# UART_Comm_Isolation.net
KiCad netlist of a schematic drawn in Altium Designer
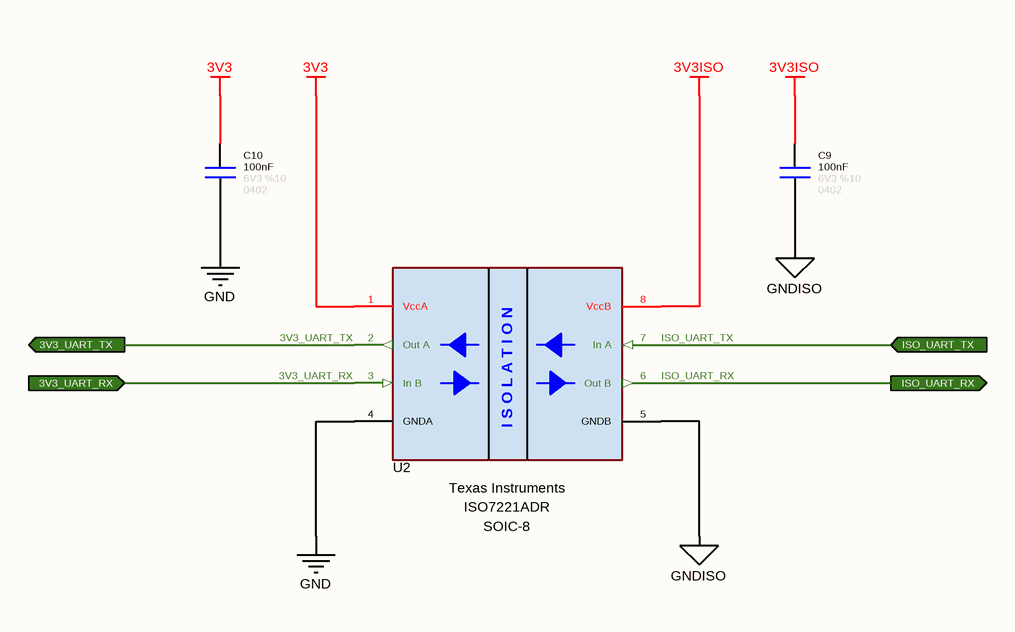
[diagram p0: UART Comm Isolation.SchDoc]

(export (version "E")
  (design (tool "Eeschema 10.0.6"))
  (components
    (comp (ref "C9")
      (value "100nF")
      (footprint "CAPACITOR_0402")
      (description "Capacitor - 100nF [0402-6V3] (Ceramic)")
      (fields
        (field (name "MANUFACTURER PART NUMBER") "04026D104KAT4A")
        (field (name "TOLERANCE") "%10")
        (field (name "VOLTAGE") "6V3")
        (field (name "CASE") "0402")
        (field (name "Comment") "Capacitor - 100nF [0402] (Ceramic)")
      )
      (libsource (lib "Akkoyun") (part "Capacitor - 100nF [0402-6V3]"))
    )
    (comp (ref "C10")
      (value "100nF")
      (footprint "CAPACITOR_0402")
      (description "Capacitor - 100nF [0402-6V3] (Ceramic)")
      (fields
        (field (name "MANUFACTURER PART NUMBER") "04026D104KAT4A")
        (field (name "TOLERANCE") "%10")
        (field (name "VOLTAGE") "6V3")
        (field (name "CASE") "0402")
        (field (name "Comment") "Capacitor - 100nF [0402] (Ceramic)")
      )
      (libsource (lib "Akkoyun") (part "Capacitor - 100nF [0402-6V3]"))
    )
    (comp (ref "U2")
      (value "ISO7221ADR")
      (footprint "SOIC-8 Narrow")
      (description "Dual-channel, TTL, 1/1, 1-Mbps digital isolator 8-SOIC -40 to 125")
      (fields
        (field (name "MANUFACTURER NAME") "Texas Instruments")
        (field (name "MANUFACTURER PART NUMBER") "ISO7221ADR")
        (field (name "CASE") "SOIC-8")
      )
      (libsource (lib "Akkoyun") (part "IC - ISO7221ADR"))
    )
  )
  (nets
    (net (code "1") (name "/3V3_UART_RX") (class "Default")
      (node (ref "U2") (pin "3") (pinfunction "In_B_3") (pintype "input"))
    )
    (net (code "2") (name "/3V3_UART_TX") (class "Default")
      (node (ref "U2") (pin "2") (pinfunction "Out_A_2") (pintype "output"))
    )
    (net (code "3") (name "/ISO_UART_RX") (class "Default")
      (node (ref "U2") (pin "6") (pinfunction "Out_B_6") (pintype "output"))
    )
    (net (code "4") (name "/ISO_UART_TX") (class "Default")
      (node (ref "U2") (pin "7") (pinfunction "In_A_7") (pintype "input"))
    )
    (net (code "5") (name "3V3") (class "Default")
      (node (ref "C10") (pin "2") (pinfunction "2_2") (pintype "passive"))
      (node (ref "U2") (pin "1") (pinfunction "VccA_1") (pintype "power_in"))
    )
    (net (code "6") (name "3V3ISO") (class "Default")
      (node (ref "C9") (pin "2") (pinfunction "2_2") (pintype "passive"))
      (node (ref "U2") (pin "8") (pinfunction "VccB_8") (pintype "power_in"))
    )
    (net (code "7") (name "GND") (class "Default")
      (node (ref "C10") (pin "1") (pinfunction "1_1") (pintype "passive"))
      (node (ref "U2") (pin "4") (pinfunction "GNDA_4") (pintype "power_in"))
    )
    (net (code "8") (name "GNDISO") (class "Default")
      (node (ref "C9") (pin "1") (pinfunction "1_1") (pintype "passive"))
      (node (ref "U2") (pin "5") (pinfunction "GNDB_5") (pintype "power_in"))
    )
  )
)
